# FAT32_2.net
KiCad netlist of a schematic drawn in Altium Designer
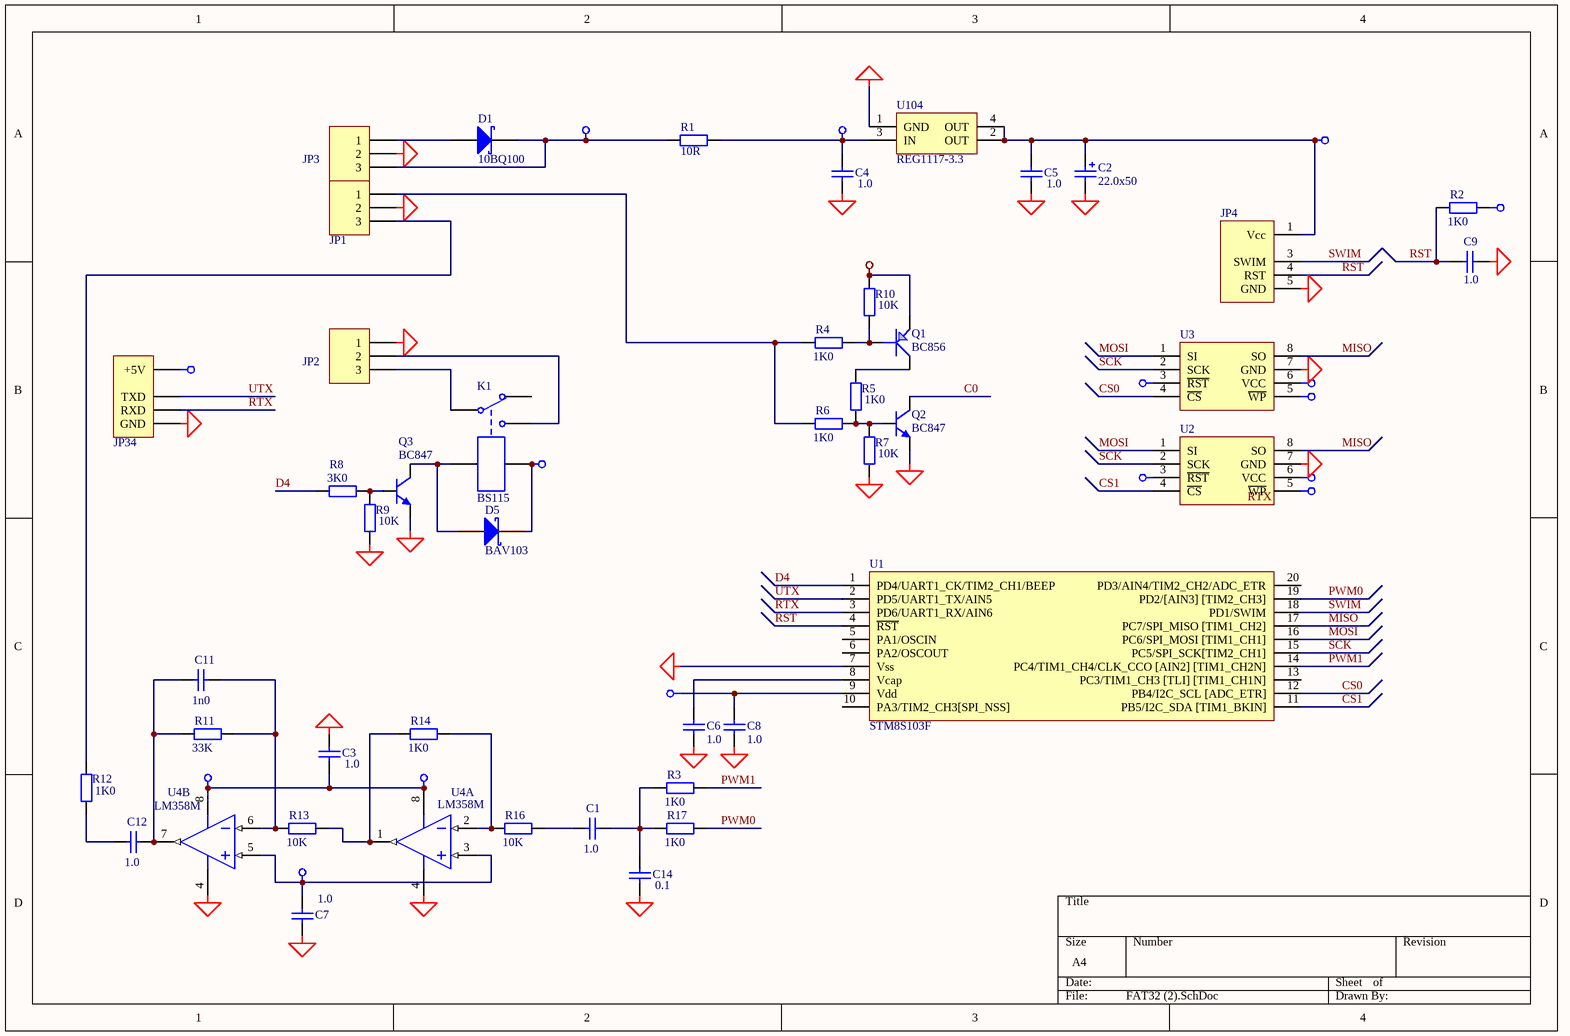
[diagram p0: FAT32 (2).SchDoc]

(export (version "E")
  (design (tool "Eeschema 10.0.6"))
  (components
    (comp (ref "C1")
      (value "1.0")
      (footprint "_1206")
      (description "Capacitor (Semiconductor SIM Model)")
      (fields (field (name "MANUFACTURER") "Generic Components") (field (name "PUBLISHER") "Altium Limited"))
      (libsource (lib "Miscellaneous Devices") (part "Cap Semi"))
    )
    (comp (ref "C2")
      (value "22.0x50")
      (footprint "CAP_EL_6_3")
      (description "Polarized Capacitor (Radial)")
      (fields (field (name "MANUFACTURER") "Generic Components") (field (name "PUBLISHER") "Altium Limited"))
      (libsource (lib "PAL") (part "Cap Pol1"))
    )
    (comp (ref "C3")
      (value "1.0")
      (footprint "_1206")
      (description "Capacitor (Semiconductor SIM Model)")
      (fields (field (name "MANUFACTURER") "Generic Components") (field (name "PUBLISHER") "Altium Limited"))
      (libsource (lib "Miscellaneous Devices") (part "Cap Semi"))
    )
    (comp (ref "C4")
      (value "1.0")
      (footprint "_1206")
      (description "Capacitor (Semiconductor SIM Model)")
      (fields (field (name "MANUFACTURER") "Generic Components") (field (name "PUBLISHER") "Altium Limited"))
      (libsource (lib "Miscellaneous Devices") (part "Cap Semi"))
    )
    (comp (ref "C5")
      (value "1.0")
      (footprint "_1206")
      (description "Capacitor (Semiconductor SIM Model)")
      (fields (field (name "MANUFACTURER") "Generic Components") (field (name "PUBLISHER") "Altium Limited"))
      (libsource (lib "Miscellaneous Devices") (part "Cap Semi"))
    )
    (comp (ref "C6")
      (value "1.0")
      (footprint "_1206")
      (description "Capacitor (Semiconductor SIM Model)")
      (fields (field (name "MANUFACTURER") "Generic Components") (field (name "PUBLISHER") "Altium Limited"))
      (libsource (lib "Miscellaneous Devices") (part "Cap Semi"))
    )
    (comp (ref "C7")
      (value "1.0")
      (footprint "_1206")
      (description "Capacitor (Semiconductor SIM Model)")
      (fields (field (name "MANUFACTURER") "Generic Components") (field (name "PUBLISHER") "Altium Limited"))
      (libsource (lib "Miscellaneous Devices") (part "Cap Semi"))
    )
    (comp (ref "C8")
      (value "1.0")
      (footprint "_1206")
      (description "Capacitor (Semiconductor SIM Model)")
      (fields (field (name "MANUFACTURER") "Generic Components") (field (name "PUBLISHER") "Altium Limited"))
      (libsource (lib "Miscellaneous Devices") (part "Cap Semi"))
    )
    (comp (ref "C9")
      (value "1.0")
      (footprint "_1206")
      (description "Capacitor (Semiconductor SIM Model)")
      (fields (field (name "MANUFACTURER") "Generic Components") (field (name "PUBLISHER") "Altium Limited"))
      (libsource (lib "") (part "Cap Semi_1"))
    )
    (comp (ref "C11")
      (value "1n0")
      (footprint "_1206")
      (description "Capacitor (Semiconductor SIM Model)")
      (fields (field (name "MANUFACTURER") "Generic Components") (field (name "PUBLISHER") "Altium Limited"))
      (libsource (lib "") (part "Cap Semi_1"))
    )
    (comp (ref "C12")
      (value "1.0")
      (footprint "_1206")
      (description "Capacitor (Semiconductor SIM Model)")
      (fields (field (name "MANUFACTURER") "Generic Components") (field (name "PUBLISHER") "Altium Limited"))
      (libsource (lib "") (part "Cap Semi_1"))
    )
    (comp (ref "C14")
      (value "0.1")
      (footprint "_1206")
      (description "Capacitor (Semiconductor SIM Model)")
      (fields (field (name "MANUFACTURER") "Generic Components") (field (name "PUBLISHER") "Altium Limited"))
      (libsource (lib "Miscellaneous Devices") (part "Cap Semi"))
    )
    (comp (ref "D1")
      (value "10BQ100")
      (footprint "DSO-C2/X2.3")
      (description "Schottky Rectifier")
      (fields
        (field (name "MANUFACTURER") "International Rectifier")
        (field (name "PUBLISHER") "Altium Limited")
      )
      (libsource (lib "IR Discrete Diode") (part "10BQ015"))
    )
    (comp (ref "D5")
      (value "BAV103")
      (footprint "_1206d")
      (description "Schottky Rectifier")
      (fields
        (field (name "MANUFACTURER") "International Rectifier")
        (field (name "PUBLISHER") "Altium Limited")
      )
      (libsource (lib "IR Discrete Diode") (part "10BQ015"))
    )
    (comp (ref "JP1")
      (value "Header 3")
      (footprint "BT5-3")
      (description "Header, 3-Pin")
      (fields (field (name "MANUFACTURER") "Generic Components") (field (name "PUBLISHER") "Altium Limited"))
      (libsource (lib "Miscellaneous Connectors") (part "Header 3"))
    )
    (comp (ref "JP2")
      (value "Header 3")
      (footprint "BT5-3")
      (description "Header, 3-Pin")
      (fields (field (name "MANUFACTURER") "Generic Components") (field (name "PUBLISHER") "Altium Limited"))
      (libsource (lib "Miscellaneous Connectors") (part "Header 3"))
    )
    (comp (ref "JP3")
      (value "Header 3")
      (footprint "BT5-3")
      (description "Header, 3-Pin")
      (fields (field (name "MANUFACTURER") "Generic Components") (field (name "PUBLISHER") "Altium Limited"))
      (libsource (lib "Miscellaneous Connectors") (part "Header 3"))
    )
    (comp (ref "JP4") (value "~") (footprint "HDR1X5_uart") (libsource (lib "PAL") (part "SWIM_CONN")))
    (comp (ref "JP34")
      (value "UART_PORT")
      (footprint "HDR1X5_uart")
      (description "Header, 5-Pin")
      (fields (field (name "MANUFACTURER") "Generic Components") (field (name "PUBLISHER") "Altium Limited"))
      (libsource (lib "igorenja") (part "UART_PORT"))
    )
    (comp (ref "K1")
      (value "BS115")
      (footprint "BS115")
      (description "Single-Pole Dual-Throw Relay")
      (fields (field (name "MANUFACTURER") "Generic Components") (field (name "PUBLISHER") "Altium Limited"))
      (libsource (lib "PAL") (part "BS115"))
    )
    (comp (ref "Q1") (value "BC856") (footprint "SO-G3") (libsource (lib "MAIN") (part "GT109")))
    (comp (ref "Q2")
      (value "BC847")
      (footprint "SO-G3/C2.5")
      (description "General Purpose Transistor NPN Silicon")
      (fields (field (name "MANUFACTURER") "Motorola") (field (name "PUBLISHER") "Altium Limited"))
      (libsource (lib "PAL") (part "BC847ALT1"))
    )
    (comp (ref "Q3")
      (value "BC847")
      (footprint "SO-G3/C2.5")
      (description "General Purpose Transistor NPN Silicon")
      (fields (field (name "MANUFACTURER") "Motorola") (field (name "PUBLISHER") "Altium Limited"))
      (libsource (lib "PAL") (part "BC847ALT1"))
    )
    (comp (ref "R1")
      (value "Res2")
      (footprint "_1206")
      (description "Resistor")
      (fields
        (field (name "MANUFACTURER") "Generic Components")
        (field (name "ALTIUM_VALUE") "10R")
        (field (name "PUBLISHER") "Altium Limited")
      )
      (libsource (lib "") (part "Res2_3"))
    )
    (comp (ref "R2")
      (value "1K0")
      (footprint "_1206")
      (description "Resistor")
      (fields (field (name "MANUFACTURER") "Generic Components") (field (name "PUBLISHER") "Altium Limited"))
      (libsource (lib "") (part "Res2_2"))
    )
    (comp (ref "R3")
      (value "1K0")
      (footprint "_1206")
      (description "Resistor")
      (fields (field (name "MANUFACTURER") "Generic Components") (field (name "PUBLISHER") "Altium Limited"))
      (libsource (lib "Miscellaneous Devices") (part "Res2"))
    )
    (comp (ref "R4")
      (value "1K0")
      (footprint "_1206")
      (description "Resistor")
      (fields (field (name "MANUFACTURER") "Generic Components") (field (name "PUBLISHER") "Altium Limited"))
      (libsource (lib "") (part "Res2_2"))
    )
    (comp (ref "R5")
      (value "1K0")
      (footprint "_1206")
      (description "Resistor")
      (fields (field (name "MANUFACTURER") "Generic Components") (field (name "PUBLISHER") "Altium Limited"))
      (libsource (lib "") (part "Res2_1"))
    )
    (comp (ref "R6")
      (value "1K0")
      (footprint "_1206")
      (description "Resistor")
      (fields (field (name "MANUFACTURER") "Generic Components") (field (name "PUBLISHER") "Altium Limited"))
      (libsource (lib "") (part "Res2_2"))
    )
    (comp (ref "R7")
      (value "10K")
      (footprint "_1206")
      (description "Resistor")
      (fields (field (name "MANUFACTURER") "Generic Components") (field (name "PUBLISHER") "Altium Limited"))
      (libsource (lib "") (part "Res2_4"))
    )
    (comp (ref "R8")
      (value "3K0")
      (footprint "_1206")
      (description "Resistor")
      (fields (field (name "MANUFACTURER") "Generic Components") (field (name "PUBLISHER") "Altium Limited"))
      (libsource (lib "") (part "Res2_2"))
    )
    (comp (ref "R9")
      (value "10K")
      (footprint "_1206")
      (description "Resistor")
      (fields (field (name "MANUFACTURER") "Generic Components") (field (name "PUBLISHER") "Altium Limited"))
      (libsource (lib "") (part "Res2_4"))
    )
    (comp (ref "R10")
      (value "10K")
      (footprint "_1206")
      (description "Resistor")
      (fields (field (name "MANUFACTURER") "Generic Components") (field (name "PUBLISHER") "Altium Limited"))
      (libsource (lib "PAL") (part "RES"))
    )
    (comp (ref "R11")
      (value "33K")
      (footprint "_1206")
      (description "Resistor")
      (fields (field (name "MANUFACTURER") "Generic Components") (field (name "PUBLISHER") "Altium Limited"))
      (libsource (lib "Miscellaneous Devices") (part "Res2"))
    )
    (comp (ref "R12")
      (value "1K0")
      (footprint "_1206")
      (description "Resistor")
      (fields (field (name "MANUFACTURER") "Generic Components") (field (name "PUBLISHER") "Altium Limited"))
      (libsource (lib "") (part "Res2_1"))
    )
    (comp (ref "R13")
      (value "10K")
      (footprint "_1206")
      (description "Resistor")
      (fields (field (name "MANUFACTURER") "Generic Components") (field (name "PUBLISHER") "Altium Limited"))
      (libsource (lib "Miscellaneous Devices") (part "Res2"))
    )
    (comp (ref "R14")
      (value "1K0")
      (footprint "_1206")
      (description "Resistor")
      (fields (field (name "MANUFACTURER") "Generic Components") (field (name "PUBLISHER") "Altium Limited"))
      (libsource (lib "Miscellaneous Devices") (part "Res2"))
    )
    (comp (ref "R16")
      (value "10K")
      (footprint "_1206")
      (description "Resistor")
      (fields (field (name "MANUFACTURER") "Generic Components") (field (name "PUBLISHER") "Altium Limited"))
      (libsource (lib "Miscellaneous Devices") (part "Res2"))
    )
    (comp (ref "R17")
      (value "1K0")
      (footprint "_1206")
      (description "Resistor")
      (fields (field (name "MANUFACTURER") "Generic Components") (field (name "PUBLISHER") "Altium Limited"))
      (libsource (lib "Miscellaneous Devices") (part "Res2"))
    )
    (comp (ref "U1") (value "~") (footprint "TSSO6x6-G20/Y1.6") (libsource (lib "PAL") (part "STM8S103F")))
    (comp (ref "U2") (value "~") (footprint "AT45W") (libsource (lib "PAL") (part "AT45DB161D-SU")))
    (comp (ref "U3") (value "~") (footprint "AT45W") (libsource (lib "PAL") (part "AT45DB161D-SU")))
    (comp (ref "U4")
      (value "LM358M")
      (footprint "SO-G8")
      (description "Low-Power Dual Operational Amplifier")
      (fields
        (field (name "MANUFACTURER") "National Semiconductor")
        (field (name "PUBLISHER") "Altium Limited")
      )
      (libsource (lib "NSC Operational Amplifier") (part "LM358M"))
    )
    (comp (ref "U104")
      (value "REG1117-3.3")
      (footprint "SIP-G3/C7.4")
      (description "800mA and 1A Low Dropout Positive Regulator 2.85V, 3.3V, 5V, and Adjustable")
      (fields (field (name "MANUFACTURER") "Burr-Brown") (field (name "PUBLISHER") "Altium Limited"))
      (libsource (lib "BB Power Mgt Voltage Regulator") (part "REG1117-3.3"))
    )
  )
  (nets
    (net (code "1") (name "+3v3") (class "Default")
      (node (ref "C2") (pin "1") (pinfunction "1_1") (pintype "passive"))
      (node (ref "C5") (pin "2") (pinfunction "2_2") (pintype "passive"))
      (node (ref "C7") (pin "2") (pinfunction "2_2") (pintype "passive"))
      (node (ref "C8") (pin "2") (pinfunction "2_2") (pintype "passive"))
      (node (ref "JP34") (pin "1") (pinfunction "+5V_1") (pintype "passive"))
      (node (ref "JP4") (pin "1") (pinfunction "Vcc_1") (pintype "passive"))
      (node (ref "R2") (pin "1") (pinfunction "1_1") (pintype "passive"))
      (node (ref "U1") (pin "9") (pinfunction "Vdd_9") (pintype "passive"))
      (node (ref "U104") (pin "2") (pinfunction "OUT_2") (pintype "power_in"))
      (node (ref "U104") (pin "4") (pinfunction "OUT_4") (pintype "power_in"))
      (node (ref "U2") (pin "3") (pinfunction "~{RST}_3") (pintype "passive"))
      (node (ref "U2") (pin "5") (pinfunction "~{WP}_5") (pintype "passive"))
      (node (ref "U2") (pin "6") (pinfunction "VCC_6") (pintype "passive"))
      (node (ref "U3") (pin "3") (pinfunction "~{RST}_3") (pintype "passive"))
      (node (ref "U3") (pin "5") (pinfunction "~{WP}_5") (pintype "passive"))
      (node (ref "U3") (pin "6") (pinfunction "VCC_6") (pintype "passive"))
      (node (ref "U4") (pin "3") (pinfunction "IN+_3") (pintype "input"))
      (node (ref "U4") (pin "5") (pinfunction "IN+_5") (pintype "input"))
    )
    (net (code "2") (name "+12v") (class "Default")
      (node (ref "D1") (pin "2") (pinfunction "K_2") (pintype "passive"))
      (node (ref "D5") (pin "2") (pinfunction "K_2") (pintype "passive"))
      (node (ref "JP3") (pin "3") (pinfunction "3_3") (pintype "passive"))
      (node (ref "K1") (pin "5") (pinfunction "5_5") (pintype "passive"))
      (node (ref "Q1") (pin "2") (pinfunction "E_2") (pintype "passive"))
      (node (ref "R1") (pin "1") (pinfunction "1_1") (pintype "passive"))
      (node (ref "R10") (pin "2") (pinfunction "2_2") (pintype "passive"))
    )
    (net (code "3") (name "+12vi") (class "Default")
      (node (ref "C3") (pin "2") (pinfunction "2_2") (pintype "passive"))
      (node (ref "C4") (pin "2") (pinfunction "2_2") (pintype "passive"))
      (node (ref "R1") (pin "2") (pinfunction "2_2") (pintype "passive"))
      (node (ref "U104") (pin "3") (pinfunction "IN_3") (pintype "power_in"))
      (node (ref "U4") (pin "8") (pinfunction "V+_8") (pintype "power_in"))
    )
    (net (code "4") (name "/C0") (class "Default")
      (node (ref "Q2") (pin "3") (pinfunction "C_3") (pintype "passive"))
    )
    (net (code "5") (name "/CS0") (class "Default")
      (node (ref "U1") (pin "12") (pinfunction "PB4/I2C_SCL_[ADC_ETR]_12") (pintype "passive"))
      (node (ref "U3") (pin "4") (pinfunction "~{CS}_4") (pintype "passive"))
    )
    (net (code "6") (name "/CS1") (class "Default")
      (node (ref "U1") (pin "11") (pinfunction "PB5/I2C_SDA_[TIM1_BKIN]_11") (pintype "passive"))
      (node (ref "U2") (pin "4") (pinfunction "~{CS}_4") (pintype "passive"))
    )
    (net (code "7") (name "/D4") (class "Default")
      (node (ref "R8") (pin "2") (pinfunction "2_2") (pintype "passive"))
      (node (ref "U1") (pin "1") (pinfunction "PD4/UART1_CK/TIM2_CH1/BEEP_1") (pintype "passive"))
    )
    (net (code "8") (name "/MISO") (class "Default")
      (node (ref "U1") (pin "17") (pinfunction "PC7/SPI_MISO_[TIM1_CH2]_17") (pintype "passive"))
      (node (ref "U2") (pin "8") (pinfunction "SO_8") (pintype "passive"))
      (node (ref "U3") (pin "8") (pinfunction "SO_8") (pintype "passive"))
    )
    (net (code "9") (name "/MOSI") (class "Default")
      (node (ref "U1") (pin "16") (pinfunction "PC6/SPI_MOSI_[TIM1_CH1]_16") (pintype "passive"))
      (node (ref "U2") (pin "1") (pinfunction "SI_1") (pintype "passive"))
      (node (ref "U3") (pin "1") (pinfunction "SI_1") (pintype "passive"))
    )
    (net (code "10") (name "/PWM0") (class "Default")
      (node (ref "R17") (pin "2") (pinfunction "2_2") (pintype "passive"))
      (node (ref "U1") (pin "19") (pinfunction "PD2/[AIN3]_[TIM2_CH3]_19") (pintype "passive"))
    )
    (net (code "11") (name "/PWM1") (class "Default")
      (node (ref "R3") (pin "2") (pinfunction "2_2") (pintype "passive"))
      (node (ref "U1") (pin "14") (pinfunction "PC4/TIM1_CH4/CLK_CCO_[AIN2]_[TIM1_CH2N]_14") (pintype "passive"))
    )
    (net (code "12") (name "/RST") (class "Default")
      (node (ref "C9") (pin "2") (pinfunction "2_2") (pintype "passive"))
      (node (ref "JP4") (pin "4") (pinfunction "RST_4") (pintype "passive"))
      (node (ref "R2") (pin "2") (pinfunction "2_2") (pintype "passive"))
      (node (ref "U1") (pin "4") (pinfunction "~{RST}_4") (pintype "passive"))
    )
    (net (code "13") (name "/RTX") (class "Default")
      (node (ref "JP34") (pin "4") (pinfunction "RXD_4") (pintype "passive"))
      (node (ref "U1") (pin "3") (pinfunction "PD6/UART1_RX/AIN6_3") (pintype "passive"))
    )
    (net (code "14") (name "/SCK") (class "Default")
      (node (ref "U1") (pin "15") (pinfunction "PC5/SPI_SCK[TIM2_CH1]_15") (pintype "passive"))
      (node (ref "U2") (pin "2") (pinfunction "SCK_2") (pintype "passive"))
      (node (ref "U3") (pin "2") (pinfunction "SCK_2") (pintype "passive"))
    )
    (net (code "15") (name "/SWIM") (class "Default")
      (node (ref "JP4") (pin "3") (pinfunction "SWIM_3") (pintype "passive"))
      (node (ref "U1") (pin "18") (pinfunction "PD1/SWIM_18") (pintype "passive"))
    )
    (net (code "16") (name "/UTX") (class "Default")
      (node (ref "JP34") (pin "3") (pinfunction "TXD_3") (pintype "passive"))
      (node (ref "U1") (pin "2") (pinfunction "PD5/UART1_TX/AIN5_2") (pintype "passive"))
    )
    (net (code "17") (name "GND") (class "Default")
      (node (ref "C14") (pin "2") (pinfunction "2_2") (pintype "passive"))
      (node (ref "C2") (pin "2") (pinfunction "2_2") (pintype "passive"))
      (node (ref "C3") (pin "1") (pinfunction "1_1") (pintype "passive"))
      (node (ref "C4") (pin "1") (pinfunction "1_1") (pintype "passive"))
      (node (ref "C5") (pin "1") (pinfunction "1_1") (pintype "passive"))
      (node (ref "C6") (pin "1") (pinfunction "1_1") (pintype "passive"))
      (node (ref "C7") (pin "1") (pinfunction "1_1") (pintype "passive"))
      (node (ref "C8") (pin "1") (pinfunction "1_1") (pintype "passive"))
      (node (ref "C9") (pin "1") (pinfunction "1_1") (pintype "passive"))
      (node (ref "JP1") (pin "2") (pinfunction "2_2") (pintype "passive"))
      (node (ref "JP2") (pin "1") (pinfunction "1_1") (pintype "passive"))
      (node (ref "JP3") (pin "2") (pinfunction "2_2") (pintype "passive"))
      (node (ref "JP34") (pin "5") (pinfunction "GND_5") (pintype "passive"))
      (node (ref "JP4") (pin "5") (pinfunction "GND_5") (pintype "passive"))
      (node (ref "Q2") (pin "2") (pinfunction "E_2") (pintype "passive"))
      (node (ref "Q3") (pin "2") (pinfunction "E_2") (pintype "passive"))
      (node (ref "R7") (pin "2") (pinfunction "2_2") (pintype "passive"))
      (node (ref "R9") (pin "2") (pinfunction "2_2") (pintype "passive"))
      (node (ref "U1") (pin "7") (pinfunction "Vss_7") (pintype "passive"))
      (node (ref "U104") (pin "1") (pinfunction "GND_1") (pintype "power_in"))
      (node (ref "U2") (pin "7") (pinfunction "GND_7") (pintype "passive"))
      (node (ref "U3") (pin "7") (pinfunction "GND_7") (pintype "passive"))
      (node (ref "U4") (pin "4") (pinfunction "GND_4") (pintype "power_in"))
    )
    (net (code "18") (name "Net-(C1-Pad1)") (class "Default")
      (node (ref "C1") (pin "1") (pinfunction "1_1") (pintype "passive"))
      (node (ref "R16") (pin "2") (pinfunction "2_2") (pintype "passive"))
    )
    (net (code "19") (name "Net-(C1-Pad2)") (class "Default")
      (node (ref "C1") (pin "2") (pinfunction "2_2") (pintype "passive"))
      (node (ref "C14") (pin "1") (pinfunction "1_1") (pintype "passive"))
      (node (ref "R17") (pin "1") (pinfunction "1_1") (pintype "passive"))
      (node (ref "R3") (pin "1") (pinfunction "1_1") (pintype "passive"))
    )
    (net (code "20") (name "Net-(C12-Pad2)") (class "Default")
      (node (ref "C12") (pin "2") (pinfunction "2_2") (pintype "passive"))
      (node (ref "R12") (pin "2") (pinfunction "2_2") (pintype "passive"))
    )
    (net (code "21") (name "Net-(D1-A)") (class "Default")
      (node (ref "D1") (pin "1") (pinfunction "A_1") (pintype "passive"))
      (node (ref "JP3") (pin "1") (pinfunction "1_1") (pintype "passive"))
    )
    (net (code "22") (name "Net-(D5-A)") (class "Default")
      (node (ref "D5") (pin "1") (pinfunction "A_1") (pintype "passive"))
      (node (ref "K1") (pin "4") (pinfunction "4_4") (pintype "passive"))
      (node (ref "Q3") (pin "3") (pinfunction "C_3") (pintype "passive"))
    )
    (net (code "23") (name "Net-(JP1-Pad1)") (class "Default")
      (node (ref "JP1") (pin "1") (pinfunction "1_1") (pintype "passive"))
      (node (ref "R4") (pin "2") (pinfunction "2_2") (pintype "passive"))
      (node (ref "R6") (pin "2") (pinfunction "2_2") (pintype "passive"))
    )
    (net (code "24") (name "Net-(JP1-Pad3)") (class "Default")
      (node (ref "JP1") (pin "3") (pinfunction "3_3") (pintype "passive"))
      (node (ref "R12") (pin "1") (pinfunction "1_1") (pintype "passive"))
    )
    (net (code "25") (name "Net-(JP2-Pad2)") (class "Default")
      (node (ref "JP2") (pin "2") (pinfunction "2_2") (pintype "passive"))
      (node (ref "K1") (pin "3") (pinfunction "3_3") (pintype "passive"))
    )
    (net (code "26") (name "Net-(JP2-Pad3)") (class "Default")
      (node (ref "JP2") (pin "3") (pinfunction "3_3") (pintype "passive"))
      (node (ref "K1") (pin "1") (pinfunction "1_1") (pintype "passive"))
    )
    (net (code "27") (name "Net-(Q1-B)") (class "Default")
      (node (ref "Q1") (pin "1") (pinfunction "B_1") (pintype "passive"))
      (node (ref "R10") (pin "1") (pinfunction "1_1") (pintype "passive"))
      (node (ref "R4") (pin "1") (pinfunction "1_1") (pintype "passive"))
    )
    (net (code "28") (name "Net-(Q1-C)") (class "Default")
      (node (ref "Q1") (pin "3") (pinfunction "C_3") (pintype "passive"))
      (node (ref "R5") (pin "1") (pinfunction "1_1") (pintype "passive"))
    )
    (net (code "29") (name "Net-(Q2-B)") (class "Default")
      (node (ref "Q2") (pin "1") (pinfunction "B_1") (pintype "passive"))
      (node (ref "R5") (pin "2") (pinfunction "2_2") (pintype "passive"))
      (node (ref "R6") (pin "1") (pinfunction "1_1") (pintype "passive"))
      (node (ref "R7") (pin "1") (pinfunction "1_1") (pintype "passive"))
    )
    (net (code "30") (name "Net-(Q3-B)") (class "Default")
      (node (ref "Q3") (pin "1") (pinfunction "B_1") (pintype "passive"))
      (node (ref "R8") (pin "1") (pinfunction "1_1") (pintype "passive"))
      (node (ref "R9") (pin "1") (pinfunction "1_1") (pintype "passive"))
    )
    (net (code "31") (name "Net-(U1-Vcap)") (class "Default")
      (node (ref "C6") (pin "2") (pinfunction "2_2") (pintype "passive"))
      (node (ref "U1") (pin "8") (pinfunction "Vcap_8") (pintype "passive"))
    )
    (net (code "32") (name "Net-(U4A-IN-)") (class "Default")
      (node (ref "R14") (pin "2") (pinfunction "2_2") (pintype "passive"))
      (node (ref "R16") (pin "1") (pinfunction "1_1") (pintype "passive"))
      (node (ref "U4") (pin "2") (pinfunction "IN-_2") (pintype "input"))
    )
    (net (code "33") (name "Net-(U4A-OUT)") (class "Default")
      (node (ref "R13") (pin "2") (pinfunction "2_2") (pintype "passive"))
      (node (ref "R14") (pin "1") (pinfunction "1_1") (pintype "passive"))
      (node (ref "U4") (pin "1") (pinfunction "OUT_1") (pintype "output"))
    )
    (net (code "34") (name "Net-(U4B-IN-)") (class "Default")
      (node (ref "C11") (pin "2") (pinfunction "2_2") (pintype "passive"))
      (node (ref "R11") (pin "2") (pinfunction "2_2") (pintype "passive"))
      (node (ref "R13") (pin "1") (pinfunction "1_1") (pintype "passive"))
      (node (ref "U4") (pin "6") (pinfunction "IN-_6") (pintype "input"))
    )
    (net (code "35") (name "Net-(U4B-OUT)") (class "Default")
      (node (ref "C11") (pin "1") (pinfunction "1_1") (pintype "passive"))
      (node (ref "C12") (pin "1") (pinfunction "1_1") (pintype "passive"))
      (node (ref "R11") (pin "1") (pinfunction "1_1") (pintype "passive"))
      (node (ref "U4") (pin "7") (pinfunction "OUT_7") (pintype "output"))
    )
    (net (code "36") (name "unconnected-(K1-Pad2)") (class "Default")
      (node (ref "K1") (pin "2") (pinfunction "2_2") (pintype "passive"))
    )
    (net (code "37") (name "unconnected-(U1-PA1{slash}OSCIN-Pad5)") (class "Default")
      (node (ref "U1") (pin "5") (pinfunction "PA1/OSCIN_5") (pintype "passive"))
    )
    (net (code "38") (name "unconnected-(U1-PA2{slash}OSCOUT-Pad6)") (class "Default")
      (node (ref "U1") (pin "6") (pinfunction "PA2/OSCOUT_6") (pintype "passive"))
    )
    (net (code "39") (name "unconnected-(U1-PA3{slash}TIM2_CH3[SPI_NSS]-Pad10)") (class "Default")
      (node (ref "U1") (pin "10") (pinfunction "PA3/TIM2_CH3[SPI_NSS]_10") (pintype "passive"))
    )
    (net (code "40") (name "unconnected-(U1-PC3{slash}TIM1_CH3_[TLI]_[TIM1_CH1N]-Pad13)") (class "Default")
      (node (ref "U1") (pin "13") (pinfunction "PC3/TIM1_CH3_[TLI]_[TIM1_CH1N]_13") (pintype "passive"))
    )
    (net (code "41") (name "unconnected-(U1-PD3{slash}AIN4{slash}TIM2_CH2{slash}ADC_ETR-Pad20)") (class "Default")
      (node (ref "U1") (pin "20") (pinfunction "PD3/AIN4/TIM2_CH2/ADC_ETR_20") (pintype "passive"))
    )
  )
)
